# fanRegulator.net
KiCad netlist of a schematic drawn in EAGLE
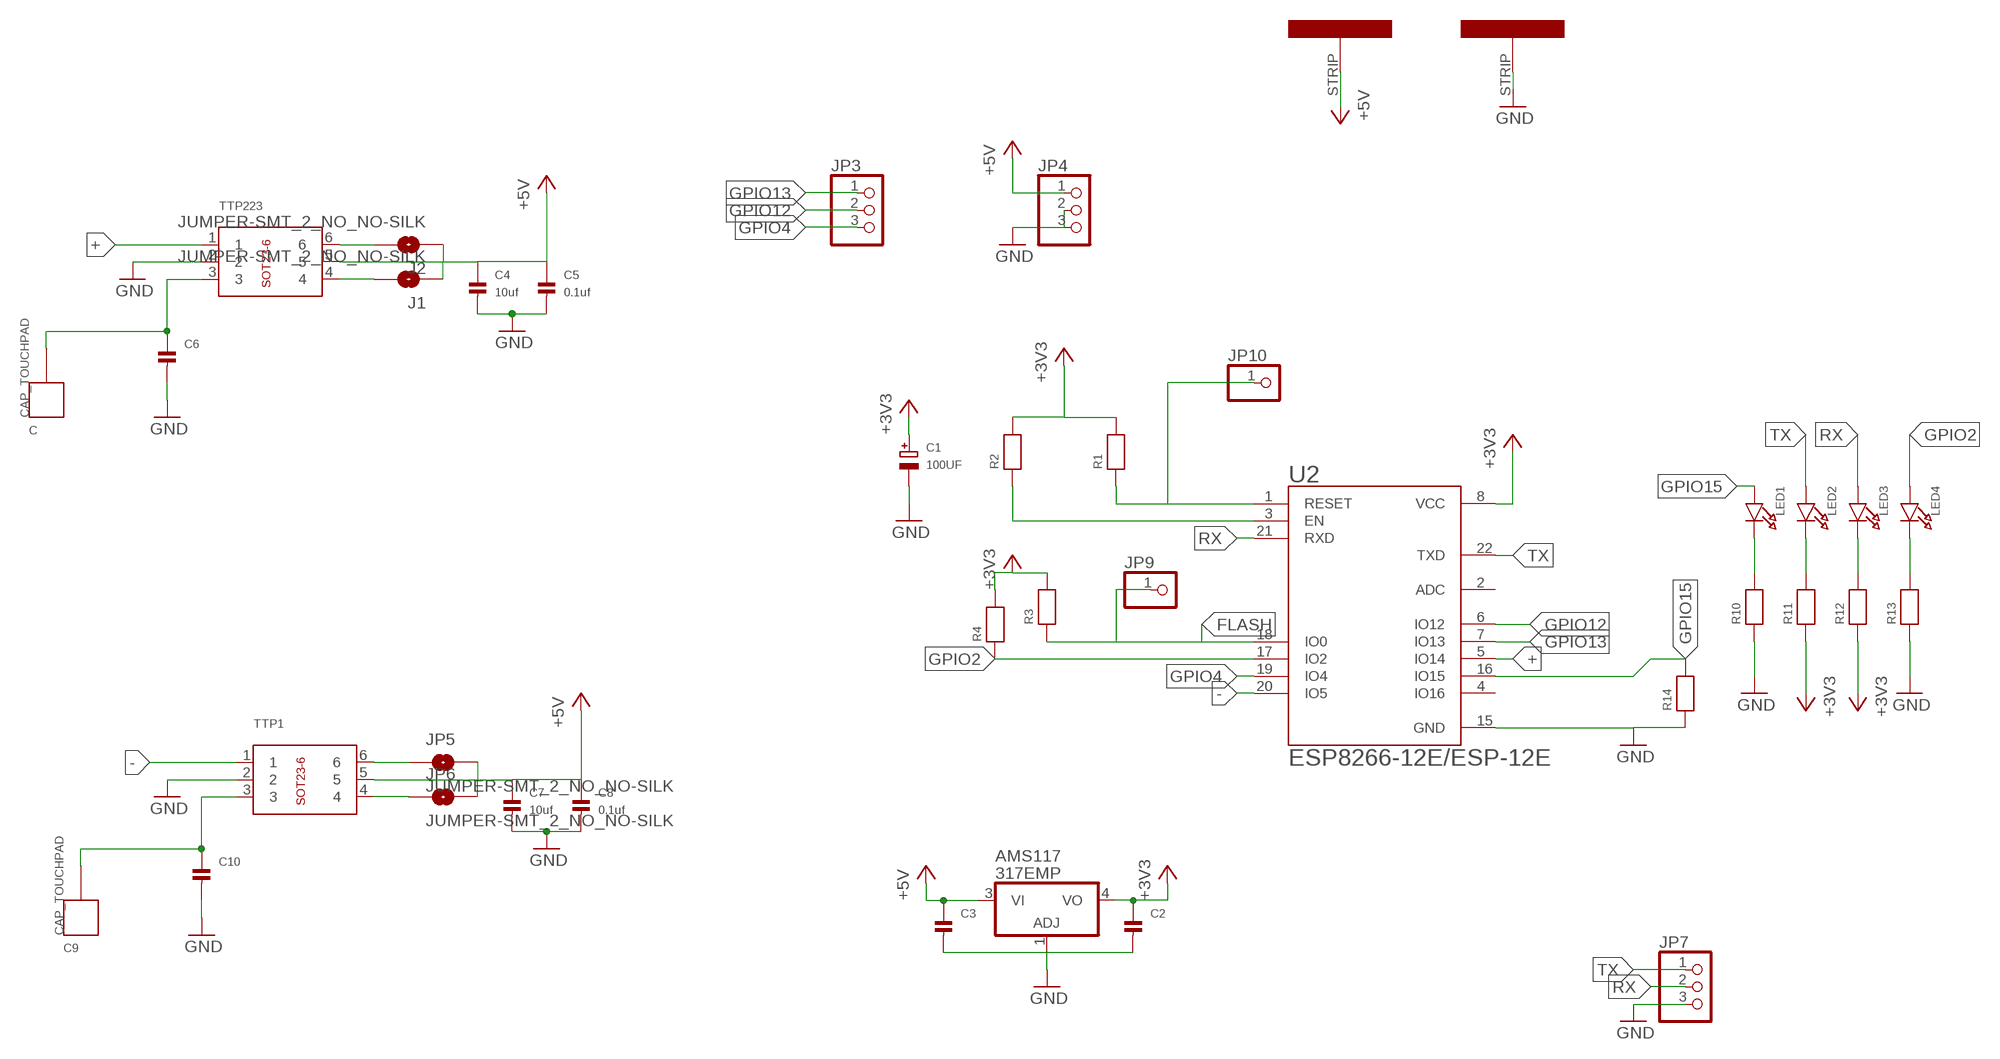
[diagram p0: schematic, sheet 1]
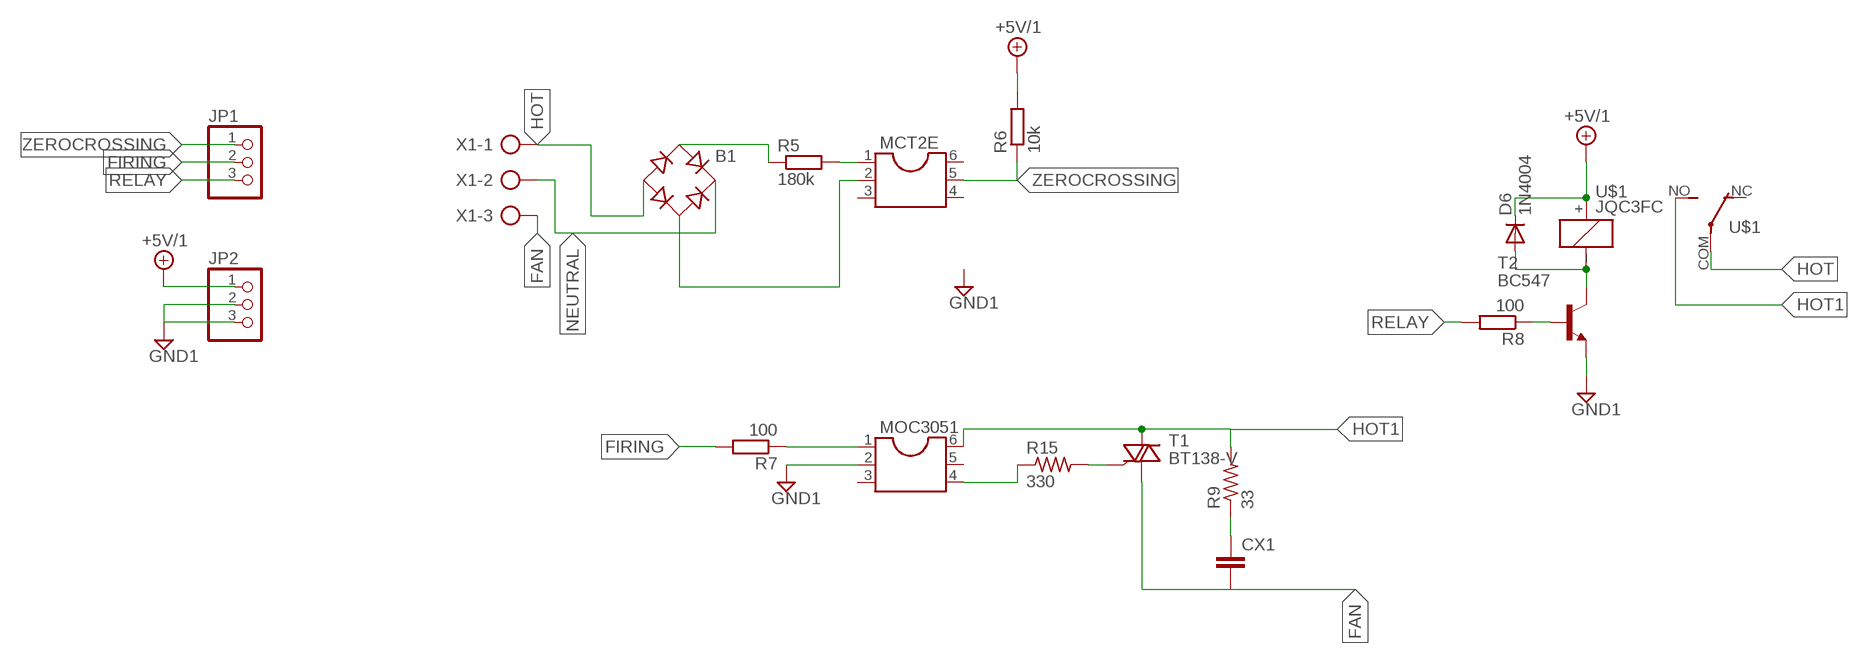
[diagram p1: schematic, sheet 2]

(export (version "E")
  (design (tool "Eeschema 10.0.6"))
  (components
    (comp (ref "AMS117")
      (value "317EMP")
      (footprint "eagle-import:SOT223")
      (libsource (lib "eagle-import") (part "317EMP"))
    )
    (comp (ref "C")
      (value "CAP_TOUCHPAD")
      (footprint "eagle-import:CAP_TOUCHPAD")
      (libsource (lib "eagle-import") (part "CAP_TOUCHPAD"))
    )
    (comp (ref "C1")
      (value "100UF")
      (footprint "eagle-import:EIA6032-28_C-W")
      (libsource (lib "eagle-import") (part "CAP_TANTALUMC/6032_WAVE"))
    )
    (comp (ref "C2")
      (value "CAP_CERAMIC0805")
      (footprint "eagle-import:0805")
      (libsource (lib "eagle-import") (part "CAP_CERAMIC0805"))
    )
    (comp (ref "C3")
      (value "CAP_CERAMIC0805")
      (footprint "eagle-import:0805")
      (libsource (lib "eagle-import") (part "CAP_CERAMIC0805"))
    )
    (comp (ref "C4")
      (value "10uf")
      (footprint "eagle-import:0805")
      (libsource (lib "eagle-import") (part "CAP_CERAMIC0805"))
    )
    (comp (ref "C5")
      (value "0.1uf")
      (footprint "eagle-import:0805")
      (libsource (lib "eagle-import") (part "CAP_CERAMIC0805"))
    )
    (comp (ref "C6")
      (value "CAP_CERAMIC0805")
      (footprint "eagle-import:0805")
      (libsource (lib "eagle-import") (part "CAP_CERAMIC0805"))
    )
    (comp (ref "C7")
      (value "10uf")
      (footprint "eagle-import:0805")
      (libsource (lib "eagle-import") (part "CAP_CERAMIC0805"))
    )
    (comp (ref "C8")
      (value "0.1uf")
      (footprint "eagle-import:0805")
      (libsource (lib "eagle-import") (part "CAP_CERAMIC0805"))
    )
    (comp (ref "C9")
      (value "CAP_TOUCHPAD")
      (footprint "eagle-import:CAP_TOUCHPAD")
      (libsource (lib "eagle-import") (part "CAP_TOUCHPAD"))
    )
    (comp (ref "C10")
      (value "CAP_CERAMIC0805")
      (footprint "eagle-import:0805")
      (libsource (lib "eagle-import") (part "CAP_CERAMIC0805"))
    )
    (comp (ref "J1")
      (value "JUMPER-SMT_2_NO_NO-SILK")
      (footprint "eagle-import:SMT-JUMPER_2_NO_NO-SILK")
      (libsource (lib "eagle-import") (part "JUMPER-SMT_2_NO_NO-SILK"))
    )
    (comp (ref "J2")
      (value "JUMPER-SMT_2_NO_NO-SILK")
      (footprint "eagle-import:SMT-JUMPER_2_NO_NO-SILK")
      (libsource (lib "eagle-import") (part "JUMPER-SMT_2_NO_NO-SILK"))
    )
    (comp (ref "JP3")
      (value "PINHD-1X3")
      (footprint "eagle-import:1X03")
      (libsource (lib "eagle-import") (part "PINHD-1X3"))
    )
    (comp (ref "JP4")
      (value "PINHD-1X3")
      (footprint "eagle-import:1X03")
      (libsource (lib "eagle-import") (part "PINHD-1X3"))
    )
    (comp (ref "JP5")
      (value "JUMPER-SMT_2_NO_NO-SILK")
      (footprint "eagle-import:SMT-JUMPER_2_NO_NO-SILK")
      (libsource (lib "eagle-import") (part "JUMPER-SMT_2_NO_NO-SILK"))
    )
    (comp (ref "JP6")
      (value "JUMPER-SMT_2_NO_NO-SILK")
      (footprint "eagle-import:SMT-JUMPER_2_NO_NO-SILK")
      (libsource (lib "eagle-import") (part "JUMPER-SMT_2_NO_NO-SILK"))
    )
    (comp (ref "JP7")
      (value "PINHD-1X3CB")
      (footprint "eagle-import:1X03-CLEANBIG")
      (libsource (lib "eagle-import") (part "PINHD-1X3CB"))
    )
    (comp (ref "JP9")
      (value "PINHD-1X1")
      (footprint "eagle-import:1X01")
      (libsource (lib "eagle-import") (part "PINHD-1X1"))
    )
    (comp (ref "JP10")
      (value "PINHD-1X1")
      (footprint "eagle-import:1X01")
      (libsource (lib "eagle-import") (part "PINHD-1X1"))
    )
    (comp (ref "LED1")
      (value "LED0805")
      (footprint "eagle-import:CHIPLED_0805")
      (libsource (lib "eagle-import") (part "LED0805"))
    )
    (comp (ref "LED2")
      (value "LED0805")
      (footprint "eagle-import:CHIPLED_0805")
      (libsource (lib "eagle-import") (part "LED0805"))
    )
    (comp (ref "LED3")
      (value "LED0805")
      (footprint "eagle-import:CHIPLED_0805")
      (libsource (lib "eagle-import") (part "LED0805"))
    )
    (comp (ref "LED4")
      (value "LED0805")
      (footprint "eagle-import:CHIPLED_0805")
      (libsource (lib "eagle-import") (part "LED0805"))
    )
    (comp (ref "R1")
      (value "RESISTOR0805")
      (footprint "eagle-import:0805")
      (libsource (lib "eagle-import") (part "RESISTOR0805"))
    )
    (comp (ref "R2")
      (value "RESISTOR0805")
      (footprint "eagle-import:0805")
      (libsource (lib "eagle-import") (part "RESISTOR0805"))
    )
    (comp (ref "R3")
      (value "RESISTOR0805")
      (footprint "eagle-import:0805")
      (libsource (lib "eagle-import") (part "RESISTOR0805"))
    )
    (comp (ref "R4")
      (value "RESISTOR0805")
      (footprint "eagle-import:0805")
      (libsource (lib "eagle-import") (part "RESISTOR0805"))
    )
    (comp (ref "R10")
      (value "RESISTOR0805")
      (footprint "eagle-import:0805")
      (libsource (lib "eagle-import") (part "RESISTOR0805"))
    )
    (comp (ref "R11")
      (value "RESISTOR0805")
      (footprint "eagle-import:0805")
      (libsource (lib "eagle-import") (part "RESISTOR0805"))
    )
    (comp (ref "R12")
      (value "RESISTOR0805")
      (footprint "eagle-import:0805")
      (libsource (lib "eagle-import") (part "RESISTOR0805"))
    )
    (comp (ref "R13")
      (value "RESISTOR0805")
      (footprint "eagle-import:0805")
      (libsource (lib "eagle-import") (part "RESISTOR0805"))
    )
    (comp (ref "R14")
      (value "RESISTOR0805")
      (footprint "eagle-import:0805")
      (libsource (lib "eagle-import") (part "RESISTOR0805"))
    )
    (comp (ref "TTP1")
      (value "BREAKOUT_SOT23-6")
      (footprint "eagle-import:BREAKOUT_SOT23-6")
      (libsource (lib "eagle-import") (part "BREAKOUT_SOT23-6"))
    )
    (comp (ref "TTP223")
      (value "BREAKOUT_SOT23-6")
      (footprint "eagle-import:BREAKOUT_SOT23-6")
      (libsource (lib "eagle-import") (part "BREAKOUT_SOT23-6"))
    )
    (comp (ref "U$2")
      (value "STRIP")
      (footprint "eagle-import:STRIP")
      (libsource (lib "eagle-import") (part "STRIP"))
    )
    (comp (ref "U$3")
      (value "STRIP")
      (footprint "eagle-import:STRIP")
      (libsource (lib "eagle-import") (part "STRIP"))
    )
    (comp (ref "U2")
      (value "ESP8266-12E/ESP-12E")
      (footprint "eagle-import:XCVR_ESP8266-12E_ESP-12E")
      (fields (field (name "MF") "AI-Thinker"))
      (libsource (lib "eagle-import") (part "ESP8266-12E/ESP-12E"))
    )
    (comp (ref "B1")
      (value "RB1A")
      (footprint "eagle-import:RB1A")
      (libsource (lib "eagle-import") (part "RB1A"))
    )
    (comp (ref "CX1")
      (value "C-EU050-024X044")
      (footprint "eagle-import:C050-024X044")
      (libsource (lib "eagle-import") (part "C-EU050-024X044"))
    )
    (comp (ref "D6")
      (value "1N4004")
      (footprint "eagle-import:DO41-10")
      (libsource (lib "eagle-import") (part "1N4004"))
    )
    (comp (ref "JP1")
      (value "PINHD-1X3")
      (footprint "eagle-import:1X03")
      (libsource (lib "eagle-import") (part "PINHD-1X3"))
    )
    (comp (ref "JP2")
      (value "PINHD-1X3")
      (footprint "eagle-import:1X03")
      (libsource (lib "eagle-import") (part "PINHD-1X3"))
    )
    (comp (ref "MCT2E")
      (value "DIL6")
      (footprint "eagle-import:DIL06")
      (libsource (lib "eagle-import") (part "DIL6"))
    )
    (comp (ref "MOC3051")
      (value "DIL6")
      (footprint "eagle-import:DIL06")
      (libsource (lib "eagle-import") (part "DIL6"))
    )
    (comp (ref "R5")
      (value "180k")
      (footprint "eagle-import:0309V")
      (libsource (lib "eagle-import") (part "R-EU_0309/V"))
    )
    (comp (ref "R6")
      (value "10k")
      (footprint "eagle-import:0204V")
      (libsource (lib "eagle-import") (part "R-EU_0204/2V"))
    )
    (comp (ref "R7")
      (value "100")
      (footprint "eagle-import:0204V")
      (libsource (lib "eagle-import") (part "R-EU_0204/2V"))
    )
    (comp (ref "R8")
      (value "100")
      (footprint "eagle-import:0204V")
      (libsource (lib "eagle-import") (part "R-EU_0204/2V"))
    )
    (comp (ref "R9")
      (value "33")
      (footprint "eagle-import:0411V")
      (libsource (lib "eagle-import") (part "R-US_0411/3V"))
    )
    (comp (ref "R15")
      (value "330")
      (footprint "eagle-import:0207_2V")
      (libsource (lib "eagle-import") (part "R-US_0207/2V"))
    )
    (comp (ref "T1")
      (value "BT138-V")
      (footprint "eagle-import:TO220BV")
      (libsource (lib "eagle-import") (part "BT138-V"))
    )
    (comp (ref "T2")
      (value "BC547")
      (footprint "eagle-import:TO92")
      (libsource (lib "eagle-import") (part "BC547"))
    )
    (comp (ref "U$1")
      (value "JQC3FC")
      (footprint "eagle-import:JQC3FC")
      (libsource (lib "eagle-import") (part "JQC3FC"))
    )
    (comp (ref "X1")
      (value "AK500/3-H")
      (footprint "eagle-import:AK500_3-H")
      (libsource (lib "eagle-import") (part "AK500/3-H"))
    )
  )
  (nets
    (net (code "1") (name "+") (class "Default")
      (node (ref "TTP223") (pin "1") (pinfunction "1_1") (pintype "bidirectional"))
      (node (ref "U2") (pin "5") (pinfunction "IO14_5") (pintype "bidirectional"))
    )
    (net (code "2") (name "+3V3") (class "Default")
      (node (ref "AMS117") (pin "4") (pinfunction "VO_4") (pintype "passive"))
      (node (ref "C1") (pin "+") (pinfunction "+_+") (pintype "passive"))
      (node (ref "C2") (pin "1") (pinfunction "P$1_1") (pintype "passive"))
      (node (ref "R1") (pin "2") (pinfunction "2_2") (pintype "passive"))
      (node (ref "R11") (pin "1") (pinfunction "1_1") (pintype "passive"))
      (node (ref "R12") (pin "1") (pinfunction "1_1") (pintype "passive"))
      (node (ref "R2") (pin "2") (pinfunction "2_2") (pintype "passive"))
      (node (ref "R3") (pin "2") (pinfunction "2_2") (pintype "passive"))
      (node (ref "R4") (pin "2") (pinfunction "2_2") (pintype "passive"))
      (node (ref "U2") (pin "8") (pinfunction "VCC_8") (pintype "power_in"))
    )
    (net (code "3") (name "+5V") (class "Default")
      (node (ref "AMS117") (pin "3") (pinfunction "VI_3") (pintype "input"))
      (node (ref "C3") (pin "1") (pinfunction "P$1_1") (pintype "passive"))
      (node (ref "C4") (pin "1") (pinfunction "P$1_1") (pintype "passive"))
      (node (ref "C5") (pin "1") (pinfunction "P$1_1") (pintype "passive"))
      (node (ref "C7") (pin "1") (pinfunction "P$1_1") (pintype "passive"))
      (node (ref "C8") (pin "1") (pinfunction "P$1_1") (pintype "passive"))
      (node (ref "J1") (pin "1") (pinfunction "1_1") (pintype "passive"))
      (node (ref "J2") (pin "1") (pinfunction "1_1") (pintype "passive"))
      (node (ref "JP4") (pin "1") (pinfunction "1_1") (pintype "passive"))
      (node (ref "JP5") (pin "2") (pinfunction "2_2") (pintype "passive"))
      (node (ref "JP6") (pin "2") (pinfunction "2_2") (pintype "passive"))
      (node (ref "TTP1") (pin "5") (pinfunction "5_5") (pintype "bidirectional"))
      (node (ref "TTP223") (pin "5") (pinfunction "5_5") (pintype "bidirectional"))
      (node (ref "U$2") (pin "STRIP") (pinfunction "STRIP_STRIP") (pintype "bidirectional"))
    )
    (net (code "4") (name "+5V{slash}1") (class "Default")
      (node (ref "D6") (pin "C") (pinfunction "C_C") (pintype "passive"))
      (node (ref "JP2") (pin "1") (pinfunction "1_1") (pintype "passive"))
      (node (ref "R6") (pin "2") (pinfunction "2_2") (pintype "passive"))
      (node (ref "U$1") (pin "+") (pinfunction "+_+") (pintype "passive"))
    )
    (net (code "5") (name "-") (class "Default")
      (node (ref "TTP1") (pin "1") (pinfunction "1_1") (pintype "bidirectional"))
      (node (ref "U2") (pin "20") (pinfunction "IO5_20") (pintype "bidirectional"))
    )
    (net (code "6") (name "FAN") (class "Default")
      (node (ref "CX1") (pin "2") (pinfunction "2_2") (pintype "passive"))
      (node (ref "T1") (pin "T1") (pinfunction "A1_T1") (pintype "passive"))
      (node (ref "X1") (pin "3") (pinfunction "KL_3") (pintype "passive"))
    )
    (net (code "7") (name "FIRING") (class "Default")
      (node (ref "JP1") (pin "2") (pinfunction "2_2") (pintype "passive"))
      (node (ref "R7") (pin "2") (pinfunction "2_2") (pintype "passive"))
    )
    (net (code "8") (name "FLASH") (class "Default")
      (node (ref "JP9") (pin "1") (pinfunction "1_1") (pintype "passive"))
      (node (ref "R3") (pin "1") (pinfunction "1_1") (pintype "passive"))
      (node (ref "U2") (pin "18") (pinfunction "IO0_18") (pintype "bidirectional"))
    )
    (net (code "9") (name "GND") (class "Default")
      (node (ref "AMS117") (pin "1") (pinfunction "ADJ_1") (pintype "input"))
      (node (ref "C1") (pin "-") (pinfunction "-_-") (pintype "passive"))
      (node (ref "C10") (pin "2") (pinfunction "P$2_2") (pintype "passive"))
      (node (ref "C2") (pin "2") (pinfunction "P$2_2") (pintype "passive"))
      (node (ref "C3") (pin "2") (pinfunction "P$2_2") (pintype "passive"))
      (node (ref "C4") (pin "2") (pinfunction "P$2_2") (pintype "passive"))
      (node (ref "C5") (pin "2") (pinfunction "P$2_2") (pintype "passive"))
      (node (ref "C6") (pin "2") (pinfunction "P$2_2") (pintype "passive"))
      (node (ref "C7") (pin "2") (pinfunction "P$2_2") (pintype "passive"))
      (node (ref "C8") (pin "2") (pinfunction "P$2_2") (pintype "passive"))
      (node (ref "JP4") (pin "2") (pinfunction "2_2") (pintype "passive"))
      (node (ref "JP4") (pin "3") (pinfunction "3_3") (pintype "passive"))
      (node (ref "JP7") (pin "3") (pinfunction "3_3") (pintype "passive"))
      (node (ref "R10") (pin "1") (pinfunction "1_1") (pintype "passive"))
      (node (ref "R13") (pin "1") (pinfunction "1_1") (pintype "passive"))
      (node (ref "R14") (pin "1") (pinfunction "1_1") (pintype "passive"))
      (node (ref "TTP1") (pin "2") (pinfunction "2_2") (pintype "bidirectional"))
      (node (ref "TTP223") (pin "2") (pinfunction "2_2") (pintype "bidirectional"))
      (node (ref "U$3") (pin "STRIP") (pinfunction "STRIP_STRIP") (pintype "bidirectional"))
      (node (ref "U2") (pin "15") (pinfunction "GND_15") (pintype "power_in"))
    )
    (net (code "10") (name "GND1") (class "Default")
      (node (ref "JP2") (pin "2") (pinfunction "2_2") (pintype "passive"))
      (node (ref "JP2") (pin "3") (pinfunction "3_3") (pintype "passive"))
      (node (ref "MOC3051") (pin "2") (pinfunction "2_2") (pintype "passive"))
      (node (ref "T2") (pin "1") (pinfunction "E_1") (pintype "passive"))
    )
    (net (code "11") (name "GPIO2") (class "Default")
      (node (ref "LED4") (pin "A") (pinfunction "A_A") (pintype "passive"))
      (node (ref "R4") (pin "1") (pinfunction "1_1") (pintype "passive"))
      (node (ref "U2") (pin "17") (pinfunction "IO2_17") (pintype "bidirectional"))
    )
    (net (code "12") (name "GPIO4") (class "Default")
      (node (ref "JP3") (pin "3") (pinfunction "3_3") (pintype "passive"))
      (node (ref "U2") (pin "19") (pinfunction "IO4_19") (pintype "bidirectional"))
    )
    (net (code "13") (name "GPIO12") (class "Default")
      (node (ref "JP3") (pin "2") (pinfunction "2_2") (pintype "passive"))
      (node (ref "U2") (pin "6") (pinfunction "IO12_6") (pintype "bidirectional"))
    )
    (net (code "14") (name "GPIO13") (class "Default")
      (node (ref "JP3") (pin "1") (pinfunction "1_1") (pintype "passive"))
      (node (ref "U2") (pin "7") (pinfunction "IO13_7") (pintype "bidirectional"))
    )
    (net (code "15") (name "GPIO15") (class "Default")
      (node (ref "LED1") (pin "A") (pinfunction "A_A") (pintype "passive"))
      (node (ref "R14") (pin "2") (pinfunction "2_2") (pintype "passive"))
      (node (ref "U2") (pin "16") (pinfunction "IO15_16") (pintype "bidirectional"))
    )
    (net (code "16") (name "HOT") (class "Default")
      (node (ref "B1") (pin "-") (pinfunction "-_-") (pintype "passive"))
      (node (ref "U$1") (pin "COM") (pinfunction "COM_COM") (pintype "passive"))
      (node (ref "X1") (pin "1") (pinfunction "KL_1") (pintype "passive"))
    )
    (net (code "17") (name "HOT1") (class "Default")
      (node (ref "MOC3051") (pin "6") (pinfunction "6_6") (pintype "passive"))
      (node (ref "R9") (pin "2") (pinfunction "2_2") (pintype "passive"))
      (node (ref "T1") (pin "T2") (pinfunction "A2_T2") (pintype "passive"))
      (node (ref "U$1") (pin "NO") (pinfunction "NO_NO") (pintype "passive"))
    )
    (net (code "18") (name "NEUTRAL") (class "Default")
      (node (ref "B1") (pin "+") (pinfunction "+_+") (pintype "passive"))
      (node (ref "X1") (pin "2") (pinfunction "KL_2") (pintype "passive"))
    )
    (net (code "19") (name "Net-(B1-PadAC1)") (class "Default")
      (node (ref "B1") (pin "AC1") (pinfunction "AC1_AC1") (pintype "passive"))
      (node (ref "R5") (pin "1") (pinfunction "1_1") (pintype "passive"))
    )
    (net (code "20") (name "Net-(B1-PadAC2)") (class "Default")
      (node (ref "B1") (pin "AC2") (pinfunction "AC2_AC2") (pintype "passive"))
      (node (ref "MCT2E") (pin "2") (pinfunction "2_2") (pintype "passive"))
    )
    (net (code "21") (name "Net-(C6-P$1)") (class "Default")
      (node (ref "C") (pin "P$1") (pinfunction "P$1_P$1") (pintype "bidirectional"))
      (node (ref "C6") (pin "1") (pinfunction "P$1_1") (pintype "passive"))
      (node (ref "TTP223") (pin "3") (pinfunction "3_3") (pintype "bidirectional"))
    )
    (net (code "22") (name "Net-(C10-P$1)") (class "Default")
      (node (ref "C10") (pin "1") (pinfunction "P$1_1") (pintype "passive"))
      (node (ref "C9") (pin "P$1") (pinfunction "P$1_P$1") (pintype "bidirectional"))
      (node (ref "TTP1") (pin "3") (pinfunction "3_3") (pintype "bidirectional"))
    )
    (net (code "23") (name "Net-(CX1-Pad1)") (class "Default")
      (node (ref "CX1") (pin "1") (pinfunction "1_1") (pintype "passive"))
      (node (ref "R9") (pin "1") (pinfunction "1_1") (pintype "passive"))
    )
    (net (code "24") (name "Net-(J1-Pad2)") (class "Default")
      (node (ref "J1") (pin "2") (pinfunction "2_2") (pintype "passive"))
      (node (ref "TTP223") (pin "4") (pinfunction "4_4") (pintype "bidirectional"))
    )
    (net (code "25") (name "Net-(J2-Pad2)") (class "Default")
      (node (ref "J2") (pin "2") (pinfunction "2_2") (pintype "passive"))
      (node (ref "TTP223") (pin "6") (pinfunction "6_6") (pintype "bidirectional"))
    )
    (net (code "26") (name "Net-(JP5-Pad1)") (class "Default")
      (node (ref "JP5") (pin "1") (pinfunction "1_1") (pintype "passive"))
      (node (ref "TTP1") (pin "6") (pinfunction "6_6") (pintype "bidirectional"))
    )
    (net (code "27") (name "Net-(JP6-Pad1)") (class "Default")
      (node (ref "JP6") (pin "1") (pinfunction "1_1") (pintype "passive"))
      (node (ref "TTP1") (pin "4") (pinfunction "4_4") (pintype "bidirectional"))
    )
    (net (code "28") (name "Net-(LED1-PadC)") (class "Default")
      (node (ref "LED1") (pin "C") (pinfunction "C_C") (pintype "passive"))
      (node (ref "R10") (pin "2") (pinfunction "2_2") (pintype "passive"))
    )
    (net (code "29") (name "Net-(LED2-PadC)") (class "Default")
      (node (ref "LED2") (pin "C") (pinfunction "C_C") (pintype "passive"))
      (node (ref "R11") (pin "2") (pinfunction "2_2") (pintype "passive"))
    )
    (net (code "30") (name "Net-(LED3-PadC)") (class "Default")
      (node (ref "LED3") (pin "C") (pinfunction "C_C") (pintype "passive"))
      (node (ref "R12") (pin "2") (pinfunction "2_2") (pintype "passive"))
    )
    (net (code "31") (name "Net-(LED4-PadC)") (class "Default")
      (node (ref "LED4") (pin "C") (pinfunction "C_C") (pintype "passive"))
      (node (ref "R13") (pin "2") (pinfunction "2_2") (pintype "passive"))
    )
    (net (code "32") (name "Net-(MCT2E-Pad1)") (class "Default")
      (node (ref "MCT2E") (pin "1") (pinfunction "1_1") (pintype "passive"))
      (node (ref "R5") (pin "2") (pinfunction "2_2") (pintype "passive"))
    )
    (net (code "33") (name "Net-(MOC3051-Pad1)") (class "Default")
      (node (ref "MOC3051") (pin "1") (pinfunction "1_1") (pintype "passive"))
      (node (ref "R7") (pin "1") (pinfunction "1_1") (pintype "passive"))
    )
    (net (code "34") (name "Net-(MOC3051-Pad4)") (class "Default")
      (node (ref "MOC3051") (pin "4") (pinfunction "4_4") (pintype "passive"))
      (node (ref "R15") (pin "1") (pinfunction "1_1") (pintype "passive"))
    )
    (net (code "35") (name "Net-(R15-Pad2)") (class "Default")
      (node (ref "R15") (pin "2") (pinfunction "2_2") (pintype "passive"))
      (node (ref "T1") (pin "G") (pinfunction "G_G") (pintype "passive"))
    )
    (net (code "36") (name "Net-(T2-B)") (class "Default")
      (node (ref "R8") (pin "1") (pinfunction "1_1") (pintype "passive"))
      (node (ref "T2") (pin "2") (pinfunction "B_2") (pintype "passive"))
    )
    (net (code "37") (name "Net-(T2-C)") (class "Default")
      (node (ref "D6") (pin "A") (pinfunction "A_A") (pintype "passive"))
      (node (ref "T2") (pin "3") (pinfunction "C_3") (pintype "passive"))
      (node (ref "U$1") (pin "_") (pinfunction "-__") (pintype "passive"))
    )
    (net (code "38") (name "Net-(U2-EN)") (class "Default")
      (node (ref "R2") (pin "1") (pinfunction "1_1") (pintype "passive"))
      (node (ref "U2") (pin "3") (pinfunction "EN_3") (pintype "input"))
    )
    (net (code "39") (name "Net-(U2-RESET)") (class "Default")
      (node (ref "JP10") (pin "1") (pinfunction "1_1") (pintype "passive"))
      (node (ref "R1") (pin "1") (pinfunction "1_1") (pintype "passive"))
      (node (ref "U2") (pin "1") (pinfunction "RESET_1") (pintype "input"))
    )
    (net (code "40") (name "RELAY") (class "Default")
      (node (ref "JP1") (pin "3") (pinfunction "3_3") (pintype "passive"))
      (node (ref "R8") (pin "2") (pinfunction "2_2") (pintype "passive"))
    )
    (net (code "41") (name "RX") (class "Default")
      (node (ref "JP7") (pin "2") (pinfunction "2_2") (pintype "passive"))
      (node (ref "LED3") (pin "A") (pinfunction "A_A") (pintype "passive"))
      (node (ref "U2") (pin "21") (pinfunction "RXD_21") (pintype "input"))
    )
    (net (code "42") (name "TX") (class "Default")
      (node (ref "JP7") (pin "1") (pinfunction "1_1") (pintype "passive"))
      (node (ref "LED2") (pin "A") (pinfunction "A_A") (pintype "passive"))
      (node (ref "U2") (pin "22") (pinfunction "TXD_22") (pintype "output"))
    )
    (net (code "43") (name "ZEROCROSSING") (class "Default")
      (node (ref "JP1") (pin "1") (pinfunction "1_1") (pintype "passive"))
      (node (ref "MCT2E") (pin "5") (pinfunction "5_5") (pintype "passive"))
      (node (ref "R6") (pin "1") (pinfunction "1_1") (pintype "passive"))
    )
    (net (code "44") (name "unconnected-(MCT2E-Pad3)") (class "Default")
      (node (ref "MCT2E") (pin "3") (pinfunction "3_3") (pintype "passive"))
    )
    (net (code "45") (name "unconnected-(MCT2E-Pad4)") (class "Default")
      (node (ref "MCT2E") (pin "4") (pinfunction "4_4") (pintype "passive"))
    )
    (net (code "46") (name "unconnected-(MCT2E-Pad6)") (class "Default")
      (node (ref "MCT2E") (pin "6") (pinfunction "6_6") (pintype "passive"))
    )
    (net (code "47") (name "unconnected-(MOC3051-Pad3)") (class "Default")
      (node (ref "MOC3051") (pin "3") (pinfunction "3_3") (pintype "passive"))
    )
    (net (code "48") (name "unconnected-(MOC3051-Pad5)") (class "Default")
      (node (ref "MOC3051") (pin "5") (pinfunction "5_5") (pintype "passive"))
    )
    (net (code "49") (name "unconnected-(U$1-PadNC)") (class "Default")
      (node (ref "U$1") (pin "NC") (pinfunction "NC_NC") (pintype "passive"))
    )
    (net (code "50") (name "unconnected-(U2-ADC-Pad2)") (class "Default")
      (node (ref "U2") (pin "2") (pinfunction "ADC_2") (pintype "passive"))
    )
    (net (code "51") (name "unconnected-(U2-IO16-Pad4)") (class "Default")
      (node (ref "U2") (pin "4") (pinfunction "IO16_4") (pintype "bidirectional"))
    )
  )
)
